# dualpowersupply.net
KiCad netlist of a schematic drawn in EAGLE
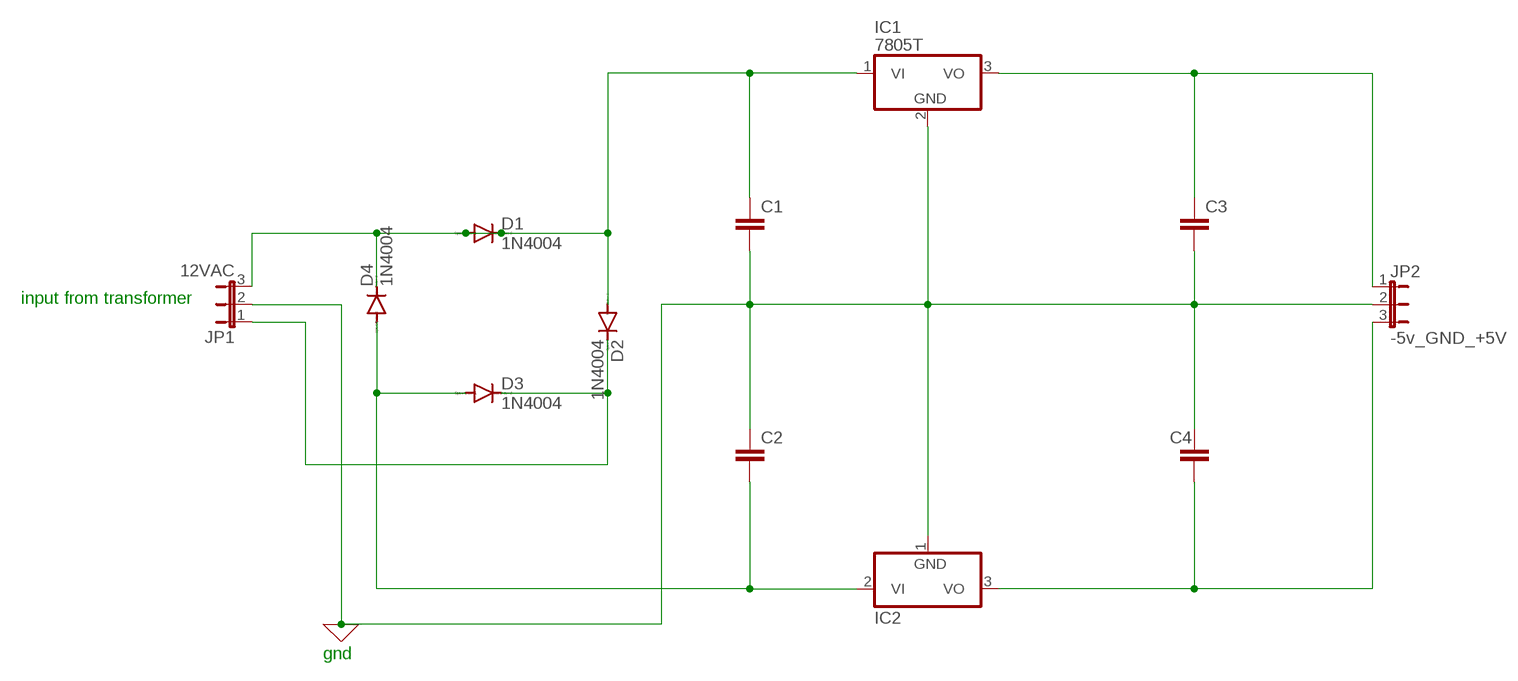
[diagram p0: schematic, sheet 1]

(export (version "E")
  (design (tool "Eeschema 10.0.6"))
  (components
    (comp (ref "C1")
      (value "C2,5-3")
      (footprint "eagle-import:C2.5-3")
      (libsource (lib "eagle-import") (part "C2,5-3"))
    )
    (comp (ref "C2")
      (value "C2,5-3")
      (footprint "eagle-import:C2.5-3")
      (libsource (lib "eagle-import") (part "C2,5-3"))
    )
    (comp (ref "C3")
      (value "C2,5-3")
      (footprint "eagle-import:C2.5-3")
      (libsource (lib "eagle-import") (part "C2,5-3"))
    )
    (comp (ref "C4")
      (value "C2,5-3")
      (footprint "eagle-import:C2.5-3")
      (libsource (lib "eagle-import") (part "C2,5-3"))
    )
    (comp (ref "D1")
      (value "1N4004")
      (footprint "eagle-import:DO41-10")
      (libsource (lib "eagle-import") (part "1N4004"))
    )
    (comp (ref "D2")
      (value "1N4004")
      (footprint "eagle-import:DO41-10")
      (libsource (lib "eagle-import") (part "1N4004"))
    )
    (comp (ref "D3")
      (value "1N4004")
      (footprint "eagle-import:DO41-10")
      (libsource (lib "eagle-import") (part "1N4004"))
    )
    (comp (ref "D4")
      (value "1N4004")
      (footprint "eagle-import:DO41-10")
      (libsource (lib "eagle-import") (part "1N4004"))
    )
    (comp (ref "IC1")
      (value "7805T")
      (footprint "eagle-import:TO220H")
      (libsource (lib "eagle-import") (part "78T05"))
    )
    (comp (ref "IC2")
      (value "7905T")
      (footprint "eagle-import:TO220H")
      (libsource (lib "eagle-import") (part "79T05"))
    )
    (comp (ref "JP1")
      (value "12VAC")
      (footprint "eagle-import:JP2W")
      (libsource (lib "eagle-import") (part "JP2W"))
    )
    (comp (ref "JP2")
      (value "-5v_GND_+5V")
      (footprint "eagle-import:JP2W")
      (libsource (lib "eagle-import") (part "JP2W"))
    )
  )
  (nets
    (net (code "1") (name "GND") (class "Default")
      (node (ref "C1") (pin "2") (pinfunction "2_2") (pintype "passive"))
      (node (ref "C2") (pin "1") (pinfunction "1_1") (pintype "passive"))
      (node (ref "C3") (pin "2") (pinfunction "2_2") (pintype "passive"))
      (node (ref "C4") (pin "1") (pinfunction "1_1") (pintype "passive"))
      (node (ref "IC1") (pin "2") (pinfunction "GND_2") (pintype "passive"))
      (node (ref "IC2") (pin "1") (pinfunction "GND_1") (pintype "passive"))
      (node (ref "JP1") (pin "2") (pinfunction "2_2") (pintype "passive"))
      (node (ref "JP2") (pin "2") (pinfunction "2_2") (pintype "passive"))
    )
    (net (code "2") (name "Net-(D2-PadC)") (class "Default")
      (node (ref "D2") (pin "C") (pinfunction "C_C") (pintype "passive"))
      (node (ref "D3") (pin "C") (pinfunction "C_C") (pintype "passive"))
      (node (ref "JP1") (pin "1") (pinfunction "1_1") (pintype "passive"))
    )
    (net (code "3") (name "Net-(IC1-VI)") (class "Default")
      (node (ref "C1") (pin "1") (pinfunction "1_1") (pintype "passive"))
      (node (ref "D1") (pin "A") (pinfunction "A_A") (pintype "passive"))
      (node (ref "D1") (pin "C") (pinfunction "C_C") (pintype "passive"))
      (node (ref "D2") (pin "A") (pinfunction "A_A") (pintype "passive"))
      (node (ref "D4") (pin "C") (pinfunction "C_C") (pintype "passive"))
      (node (ref "IC1") (pin "1") (pinfunction "VI_1") (pintype "input"))
      (node (ref "JP1") (pin "3") (pinfunction "3_3") (pintype "passive"))
    )
    (net (code "4") (name "Net-(IC1-VO)") (class "Default")
      (node (ref "C3") (pin "1") (pinfunction "1_1") (pintype "passive"))
      (node (ref "IC1") (pin "3") (pinfunction "VO_3") (pintype "passive"))
      (node (ref "JP2") (pin "1") (pinfunction "1_1") (pintype "passive"))
    )
    (net (code "5") (name "Net-(IC2-VI)") (class "Default")
      (node (ref "C2") (pin "2") (pinfunction "2_2") (pintype "passive"))
      (node (ref "D3") (pin "A") (pinfunction "A_A") (pintype "passive"))
      (node (ref "D4") (pin "A") (pinfunction "A_A") (pintype "passive"))
      (node (ref "IC2") (pin "2") (pinfunction "VI_2") (pintype "input"))
    )
    (net (code "6") (name "Net-(IC2-VO)") (class "Default")
      (node (ref "C4") (pin "2") (pinfunction "2_2") (pintype "passive"))
      (node (ref "IC2") (pin "3") (pinfunction "VO_3") (pintype "passive"))
      (node (ref "JP2") (pin "3") (pinfunction "3_3") (pintype "passive"))
    )
  )
)
